# PVScontroller_v1_with_logo.net
KiCad netlist of a schematic drawn in EAGLE
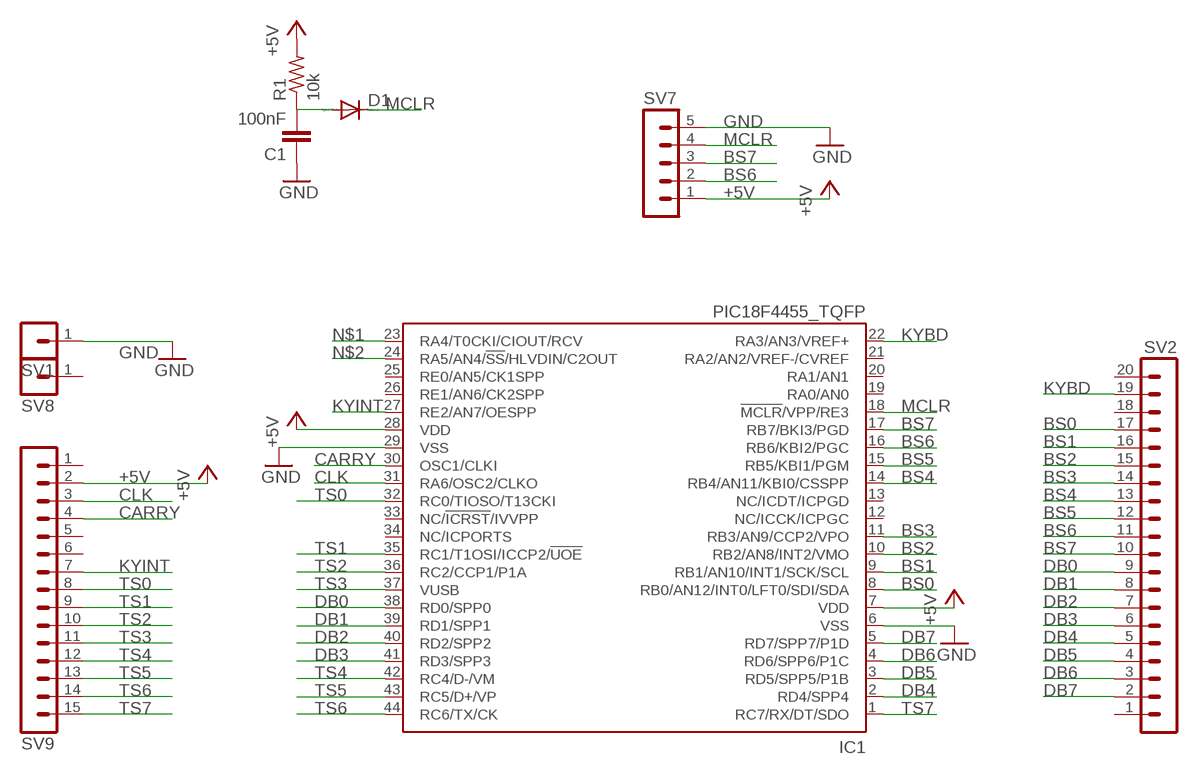
[diagram p0: schematic, sheet 1]

(export (version "E")
  (design (tool "Eeschema 10.0.6"))
  (components
    (comp (ref "C1")
      (value "100nF")
      (footprint "eagle-import:C0805")
      (libsource (lib "eagle-import") (part "C-EUC0805"))
    )
    (comp (ref "D1")
      (value "DIODE-SOD80C")
      (footprint "eagle-import:SOD80C")
      (libsource (lib "eagle-import") (part "DIODE-SOD80C"))
    )
    (comp (ref "IC1")
      (value "PIC18F4455_TQFP")
      (footprint "eagle-import:TQFP44")
      (fields (field (name "MF") "MICROCHIP") (field (name "MPN") "PIC18F4455-I/PT"))
      (libsource (lib "eagle-import") (part "PIC18F4_TQFP455"))
    )
    (comp (ref "R1")
      (value "10k")
      (footprint "eagle-import:R0805")
      (libsource (lib "eagle-import") (part "R-US_R0805"))
    )
    (comp (ref "SV1")
      (value "MA01-1")
      (footprint "eagle-import:MA01-1")
      (libsource (lib "eagle-import") (part "MA01-1"))
    )
    (comp (ref "SV2")
      (value "MA20-1")
      (footprint "eagle-import:MA20-1")
      (libsource (lib "eagle-import") (part "MA20-1"))
    )
    (comp (ref "SV7")
      (value "MA05-1")
      (footprint "eagle-import:MA05-1")
      (libsource (lib "eagle-import") (part "MA05-1"))
    )
    (comp (ref "SV8")
      (value "MA01-1")
      (footprint "eagle-import:MA01-1")
      (libsource (lib "eagle-import") (part "MA01-1"))
    )
    (comp (ref "SV9")
      (value "MA15-1")
      (footprint "eagle-import:MA15-1")
      (libsource (lib "eagle-import") (part "MA15-1"))
    )
  )
  (nets
    (net (code "1") (name "+5V") (class "Default")
      (node (ref "IC1") (pin "28") (pinfunction "VDD_28") (pintype "power_in"))
      (node (ref "IC1") (pin "7") (pinfunction "VDD_7") (pintype "power_in"))
      (node (ref "R1") (pin "2") (pinfunction "2_2") (pintype "passive"))
      (node (ref "SV7") (pin "1") (pinfunction "1_1") (pintype "passive"))
      (node (ref "SV9") (pin "2") (pinfunction "2_2") (pintype "passive"))
    )
    (net (code "2") (name "/BS0") (class "Default")
      (node (ref "IC1") (pin "8") (pinfunction "RB0/AN12/INT0/LFT0/SDI/SDA_8") (pintype "bidirectional"))
      (node (ref "SV2") (pin "17") (pinfunction "17_17") (pintype "passive"))
    )
    (net (code "3") (name "/BS1") (class "Default")
      (node (ref "IC1") (pin "9") (pinfunction "RB1/AN10/INT1/SCK/SCL_9") (pintype "bidirectional"))
      (node (ref "SV2") (pin "16") (pinfunction "16_16") (pintype "passive"))
    )
    (net (code "4") (name "/BS2") (class "Default")
      (node (ref "IC1") (pin "10") (pinfunction "RB2/AN8/INT2/VMO_10") (pintype "bidirectional"))
      (node (ref "SV2") (pin "15") (pinfunction "15_15") (pintype "passive"))
    )
    (net (code "5") (name "/BS3") (class "Default")
      (node (ref "IC1") (pin "11") (pinfunction "RB3/AN9/CCP2/VPO_11") (pintype "bidirectional"))
      (node (ref "SV2") (pin "14") (pinfunction "14_14") (pintype "passive"))
    )
    (net (code "6") (name "/BS4") (class "Default")
      (node (ref "IC1") (pin "14") (pinfunction "RB4/AN11/KBI0/CSSPP_14") (pintype "bidirectional"))
      (node (ref "SV2") (pin "13") (pinfunction "13_13") (pintype "passive"))
    )
    (net (code "7") (name "/BS5") (class "Default")
      (node (ref "IC1") (pin "15") (pinfunction "RB5/KBI1/PGM_15") (pintype "bidirectional"))
      (node (ref "SV2") (pin "12") (pinfunction "12_12") (pintype "passive"))
    )
    (net (code "8") (name "/BS6") (class "Default")
      (node (ref "IC1") (pin "16") (pinfunction "RB6/KBI2/PGC_16") (pintype "bidirectional"))
      (node (ref "SV2") (pin "11") (pinfunction "11_11") (pintype "passive"))
      (node (ref "SV7") (pin "2") (pinfunction "2_2") (pintype "passive"))
    )
    (net (code "9") (name "/BS7") (class "Default")
      (node (ref "IC1") (pin "17") (pinfunction "RB7/BKI3/PGD_17") (pintype "bidirectional"))
      (node (ref "SV2") (pin "10") (pinfunction "10_10") (pintype "passive"))
      (node (ref "SV7") (pin "3") (pinfunction "3_3") (pintype "passive"))
    )
    (net (code "10") (name "/CARRY") (class "Default")
      (node (ref "IC1") (pin "30") (pinfunction "OSC1/CLKI_30") (pintype "input"))
      (node (ref "SV9") (pin "4") (pinfunction "4_4") (pintype "passive"))
    )
    (net (code "11") (name "/CLK") (class "Default")
      (node (ref "IC1") (pin "31") (pinfunction "RA6/OSC2/CLKO_31") (pintype "output"))
      (node (ref "SV9") (pin "3") (pinfunction "3_3") (pintype "passive"))
    )
    (net (code "12") (name "/DB0") (class "Default")
      (node (ref "IC1") (pin "38") (pinfunction "RD0/SPP0_38") (pintype "bidirectional"))
      (node (ref "SV2") (pin "9") (pinfunction "9_9") (pintype "passive"))
    )
    (net (code "13") (name "/DB1") (class "Default")
      (node (ref "IC1") (pin "39") (pinfunction "RD1/SPP1_39") (pintype "bidirectional"))
      (node (ref "SV2") (pin "8") (pinfunction "8_8") (pintype "passive"))
    )
    (net (code "14") (name "/DB2") (class "Default")
      (node (ref "IC1") (pin "40") (pinfunction "RD2/SPP2_40") (pintype "bidirectional"))
      (node (ref "SV2") (pin "7") (pinfunction "7_7") (pintype "passive"))
    )
    (net (code "15") (name "/DB3") (class "Default")
      (node (ref "IC1") (pin "41") (pinfunction "RD3/SPP3_41") (pintype "bidirectional"))
      (node (ref "SV2") (pin "6") (pinfunction "6_6") (pintype "passive"))
    )
    (net (code "16") (name "/DB4") (class "Default")
      (node (ref "IC1") (pin "2") (pinfunction "RD4/SPP4_2") (pintype "bidirectional"))
      (node (ref "SV2") (pin "5") (pinfunction "5_5") (pintype "passive"))
    )
    (net (code "17") (name "/DB5") (class "Default")
      (node (ref "IC1") (pin "3") (pinfunction "RD5/SPP5/P1B_3") (pintype "bidirectional"))
      (node (ref "SV2") (pin "4") (pinfunction "4_4") (pintype "passive"))
    )
    (net (code "18") (name "/DB6") (class "Default")
      (node (ref "IC1") (pin "4") (pinfunction "RD6/SPP6/P1C_4") (pintype "bidirectional"))
      (node (ref "SV2") (pin "3") (pinfunction "3_3") (pintype "passive"))
    )
    (net (code "19") (name "/DB7") (class "Default")
      (node (ref "IC1") (pin "5") (pinfunction "RD7/SPP7/P1D_5") (pintype "bidirectional"))
      (node (ref "SV2") (pin "2") (pinfunction "2_2") (pintype "passive"))
    )
    (net (code "20") (name "/KYBD") (class "Default")
      (node (ref "IC1") (pin "22") (pinfunction "RA3/AN3/VREF+_22") (pintype "bidirectional"))
      (node (ref "SV2") (pin "19") (pinfunction "19_19") (pintype "passive"))
    )
    (net (code "21") (name "/KYINT") (class "Default")
      (node (ref "IC1") (pin "27") (pinfunction "RE2/AN7/OESPP_27") (pintype "bidirectional"))
      (node (ref "SV9") (pin "7") (pinfunction "7_7") (pintype "passive"))
    )
    (net (code "22") (name "/MCLR") (class "Default")
      (node (ref "D1") (pin "C") (pinfunction "C_C") (pintype "passive"))
      (node (ref "IC1") (pin "18") (pinfunction "~{MCLR}/VPP/RE3_18") (pintype "input"))
      (node (ref "SV7") (pin "4") (pinfunction "4_4") (pintype "passive"))
    )
    (net (code "23") (name "/N$1") (class "Default")
      (node (ref "IC1") (pin "23") (pinfunction "RA4/T0CKI/CIOUT/RCV_23") (pintype "bidirectional"))
    )
    (net (code "24") (name "/N$2") (class "Default")
      (node (ref "IC1") (pin "24") (pinfunction "RA5/AN4/~{SS}/HLVDIN/C2OUT_24") (pintype "bidirectional"))
    )
    (net (code "25") (name "/TS0") (class "Default")
      (node (ref "IC1") (pin "32") (pinfunction "RC0/TIOSO/T13CKI_32") (pintype "bidirectional"))
      (node (ref "SV9") (pin "8") (pinfunction "8_8") (pintype "passive"))
    )
    (net (code "26") (name "/TS1") (class "Default")
      (node (ref "IC1") (pin "35") (pinfunction "RC1/T1OSI/ICCP2/~{UOE}_35") (pintype "bidirectional"))
      (node (ref "SV9") (pin "9") (pinfunction "9_9") (pintype "passive"))
    )
    (net (code "27") (name "/TS2") (class "Default")
      (node (ref "IC1") (pin "36") (pinfunction "RC2/CCP1/P1A_36") (pintype "bidirectional"))
      (node (ref "SV9") (pin "10") (pinfunction "10_10") (pintype "passive"))
    )
    (net (code "28") (name "/TS3") (class "Default")
      (node (ref "IC1") (pin "37") (pinfunction "VUSB_37") (pintype "bidirectional"))
      (node (ref "SV9") (pin "11") (pinfunction "11_11") (pintype "passive"))
    )
    (net (code "29") (name "/TS4") (class "Default")
      (node (ref "IC1") (pin "42") (pinfunction "RC4/D-/VM_42") (pintype "bidirectional"))
      (node (ref "SV9") (pin "12") (pinfunction "12_12") (pintype "passive"))
    )
    (net (code "30") (name "/TS5") (class "Default")
      (node (ref "IC1") (pin "43") (pinfunction "RC5/D+/VP_43") (pintype "bidirectional"))
      (node (ref "SV9") (pin "13") (pinfunction "13_13") (pintype "passive"))
    )
    (net (code "31") (name "/TS6") (class "Default")
      (node (ref "IC1") (pin "44") (pinfunction "RC6/TX/CK_44") (pintype "bidirectional"))
      (node (ref "SV9") (pin "14") (pinfunction "14_14") (pintype "passive"))
    )
    (net (code "32") (name "/TS7") (class "Default")
      (node (ref "IC1") (pin "1") (pinfunction "RC7/RX/DT/SDO_1") (pintype "bidirectional"))
      (node (ref "SV9") (pin "15") (pinfunction "15_15") (pintype "passive"))
    )
    (net (code "33") (name "GND") (class "Default")
      (node (ref "C1") (pin "1") (pinfunction "1_1") (pintype "passive"))
      (node (ref "IC1") (pin "29") (pinfunction "VSS_29") (pintype "power_in"))
      (node (ref "IC1") (pin "6") (pinfunction "VSS_6") (pintype "power_in"))
      (node (ref "SV1") (pin "1") (pinfunction "1_1") (pintype "passive"))
      (node (ref "SV7") (pin "5") (pinfunction "5_5") (pintype "passive"))
    )
    (net (code "34") (name "Net-(C1-Pad2)") (class "Default")
      (node (ref "C1") (pin "2") (pinfunction "2_2") (pintype "passive"))
      (node (ref "D1") (pin "A") (pinfunction "A_A") (pintype "passive"))
      (node (ref "R1") (pin "1") (pinfunction "1_1") (pintype "passive"))
    )
    (net (code "35") (name "unconnected-(IC1-NC{slash}ICCK{slash}ICPGC-Pad12)") (class "Default")
      (node (ref "IC1") (pin "12") (pinfunction "NC/ICCK/ICPGC_12") (pintype "bidirectional"))
    )
    (net (code "36") (name "unconnected-(IC1-NC{slash}ICDT{slash}ICPGD-Pad13)") (class "Default")
      (node (ref "IC1") (pin "13") (pinfunction "NC/ICDT/ICPGD_13") (pintype "bidirectional"))
    )
    (net (code "37") (name "unconnected-(IC1-NC{slash}ICPORTS-Pad34)") (class "Default")
      (node (ref "IC1") (pin "34") (pinfunction "NC/ICPORTS_34") (pintype "input"))
    )
    (net (code "38") (name "unconnected-(IC1-NC{slash}~{ICRST}{slash}IVVPP-Pad33)") (class "Default")
      (node (ref "IC1") (pin "33") (pinfunction "NC/~{ICRST}/IVVPP_33") (pintype "input"))
    )
    (net (code "39") (name "unconnected-(IC1-RA0{slash}AN0-Pad19)") (class "Default")
      (node (ref "IC1") (pin "19") (pinfunction "RA0/AN0_19") (pintype "bidirectional"))
    )
    (net (code "40") (name "unconnected-(IC1-RA1{slash}AN1-Pad20)") (class "Default")
      (node (ref "IC1") (pin "20") (pinfunction "RA1/AN1_20") (pintype "bidirectional"))
    )
    (net (code "41") (name "unconnected-(IC1-RA2{slash}AN2{slash}VREF-{slash}CVREF-Pad21)") (class "Default")
      (node (ref "IC1") (pin "21") (pinfunction "RA2/AN2/VREF-/CVREF_21") (pintype "bidirectional"))
    )
    (net (code "42") (name "unconnected-(IC1-RE0{slash}AN5{slash}CK1SPP-Pad25)") (class "Default")
      (node (ref "IC1") (pin "25") (pinfunction "RE0/AN5/CK1SPP_25") (pintype "bidirectional"))
    )
    (net (code "43") (name "unconnected-(IC1-RE1{slash}AN6{slash}CK2SPP-Pad26)") (class "Default")
      (node (ref "IC1") (pin "26") (pinfunction "RE1/AN6/CK2SPP_26") (pintype "bidirectional"))
    )
    (net (code "44") (name "unconnected-(SV2-Pad1)") (class "Default")
      (node (ref "SV2") (pin "1") (pinfunction "1_1") (pintype "passive"))
    )
    (net (code "45") (name "unconnected-(SV2-Pad18)") (class "Default")
      (node (ref "SV2") (pin "18") (pinfunction "18_18") (pintype "passive"))
    )
    (net (code "46") (name "unconnected-(SV2-Pad20)") (class "Default")
      (node (ref "SV2") (pin "20") (pinfunction "20_20") (pintype "passive"))
    )
    (net (code "47") (name "unconnected-(SV8-Pad1)") (class "Default")
      (node (ref "SV8") (pin "1") (pinfunction "1_1") (pintype "passive"))
    )
    (net (code "48") (name "unconnected-(SV9-Pad1)") (class "Default")
      (node (ref "SV9") (pin "1") (pinfunction "1_1") (pintype "passive"))
    )
    (net (code "49") (name "unconnected-(SV9-Pad5)") (class "Default")
      (node (ref "SV9") (pin "5") (pinfunction "5_5") (pintype "passive"))
    )
    (net (code "50") (name "unconnected-(SV9-Pad6)") (class "Default")
      (node (ref "SV9") (pin "6") (pinfunction "6_6") (pintype "passive"))
    )
  )
)
